# ped.net
KiCad netlist of a schematic drawn in Altium Designer
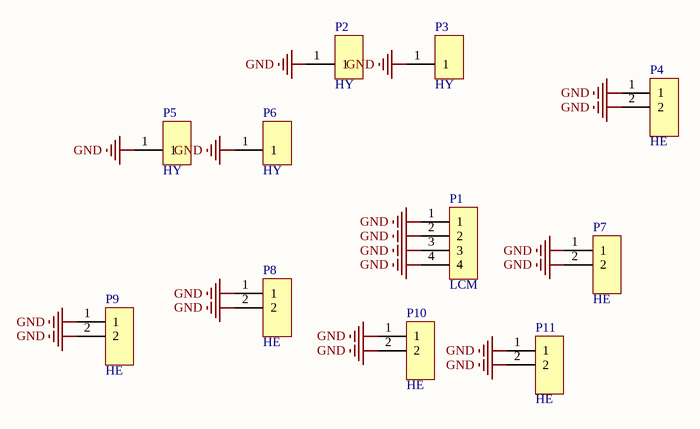
[diagram p0: ped.SchDoc]

(export (version "E")
  (design (tool "Eeschema 10.0.6"))
  (components
    (comp (ref "P1") (value "LCM") (footprint "LCD_M") (libsource (lib "ped") (part "Component_1")))
    (comp (ref "P2") (value "HY") (footprint "BNC_WE") (libsource (lib "ped") (part "HY")))
    (comp (ref "P3") (value "HY") (footprint "BNC_WE") (libsource (lib "ped") (part "HY")))
    (comp (ref "P4") (value "HE") (footprint "WK") (libsource (lib "ped") (part "HE")))
    (comp (ref "P5") (value "HY") (footprint "BNC_M") (libsource (lib "ped") (part "HY")))
    (comp (ref "P6") (value "HY") (footprint "BNC_M") (libsource (lib "ped") (part "HY")))
    (comp (ref "P7") (value "HE") (footprint "WK") (libsource (lib "ped") (part "HE")))
    (comp (ref "P8") (value "HE") (footprint "WK") (libsource (lib "ped") (part "HE")))
    (comp (ref "P9") (value "HE") (footprint "WK") (libsource (lib "ped") (part "HE")))
    (comp (ref "P10") (value "HE") (footprint "WK") (libsource (lib "ped") (part "HE")))
    (comp (ref "P11") (value "HE") (footprint "WK") (libsource (lib "ped") (part "HE")))
  )
  (nets
    (net (code "1") (name "GND") (class "Default")
      (node (ref "P1") (pin "1") (pinfunction "1_1") (pintype "passive"))
      (node (ref "P1") (pin "2") (pinfunction "2_2") (pintype "passive"))
      (node (ref "P1") (pin "3") (pinfunction "3_3") (pintype "passive"))
      (node (ref "P1") (pin "4") (pinfunction "4_4") (pintype "passive"))
      (node (ref "P10") (pin "1") (pinfunction "1_1") (pintype "passive"))
      (node (ref "P10") (pin "2") (pinfunction "2_2") (pintype "passive"))
      (node (ref "P11") (pin "1") (pinfunction "1_1") (pintype "passive"))
      (node (ref "P11") (pin "2") (pinfunction "2_2") (pintype "passive"))
      (node (ref "P2") (pin "1") (pinfunction "1_1") (pintype "passive"))
      (node (ref "P3") (pin "1") (pinfunction "1_1") (pintype "passive"))
      (node (ref "P4") (pin "1") (pinfunction "1_1") (pintype "passive"))
      (node (ref "P4") (pin "2") (pinfunction "2_2") (pintype "passive"))
      (node (ref "P5") (pin "1") (pinfunction "1_1") (pintype "passive"))
      (node (ref "P6") (pin "1") (pinfunction "1_1") (pintype "passive"))
      (node (ref "P7") (pin "1") (pinfunction "1_1") (pintype "passive"))
      (node (ref "P7") (pin "2") (pinfunction "2_2") (pintype "passive"))
      (node (ref "P8") (pin "1") (pinfunction "1_1") (pintype "passive"))
      (node (ref "P8") (pin "2") (pinfunction "2_2") (pintype "passive"))
      (node (ref "P9") (pin "1") (pinfunction "1_1") (pintype "passive"))
      (node (ref "P9") (pin "2") (pinfunction "2_2") (pintype "passive"))
    )
  )
)
